# shema.net
KiCad netlist of a schematic drawn in EAGLE
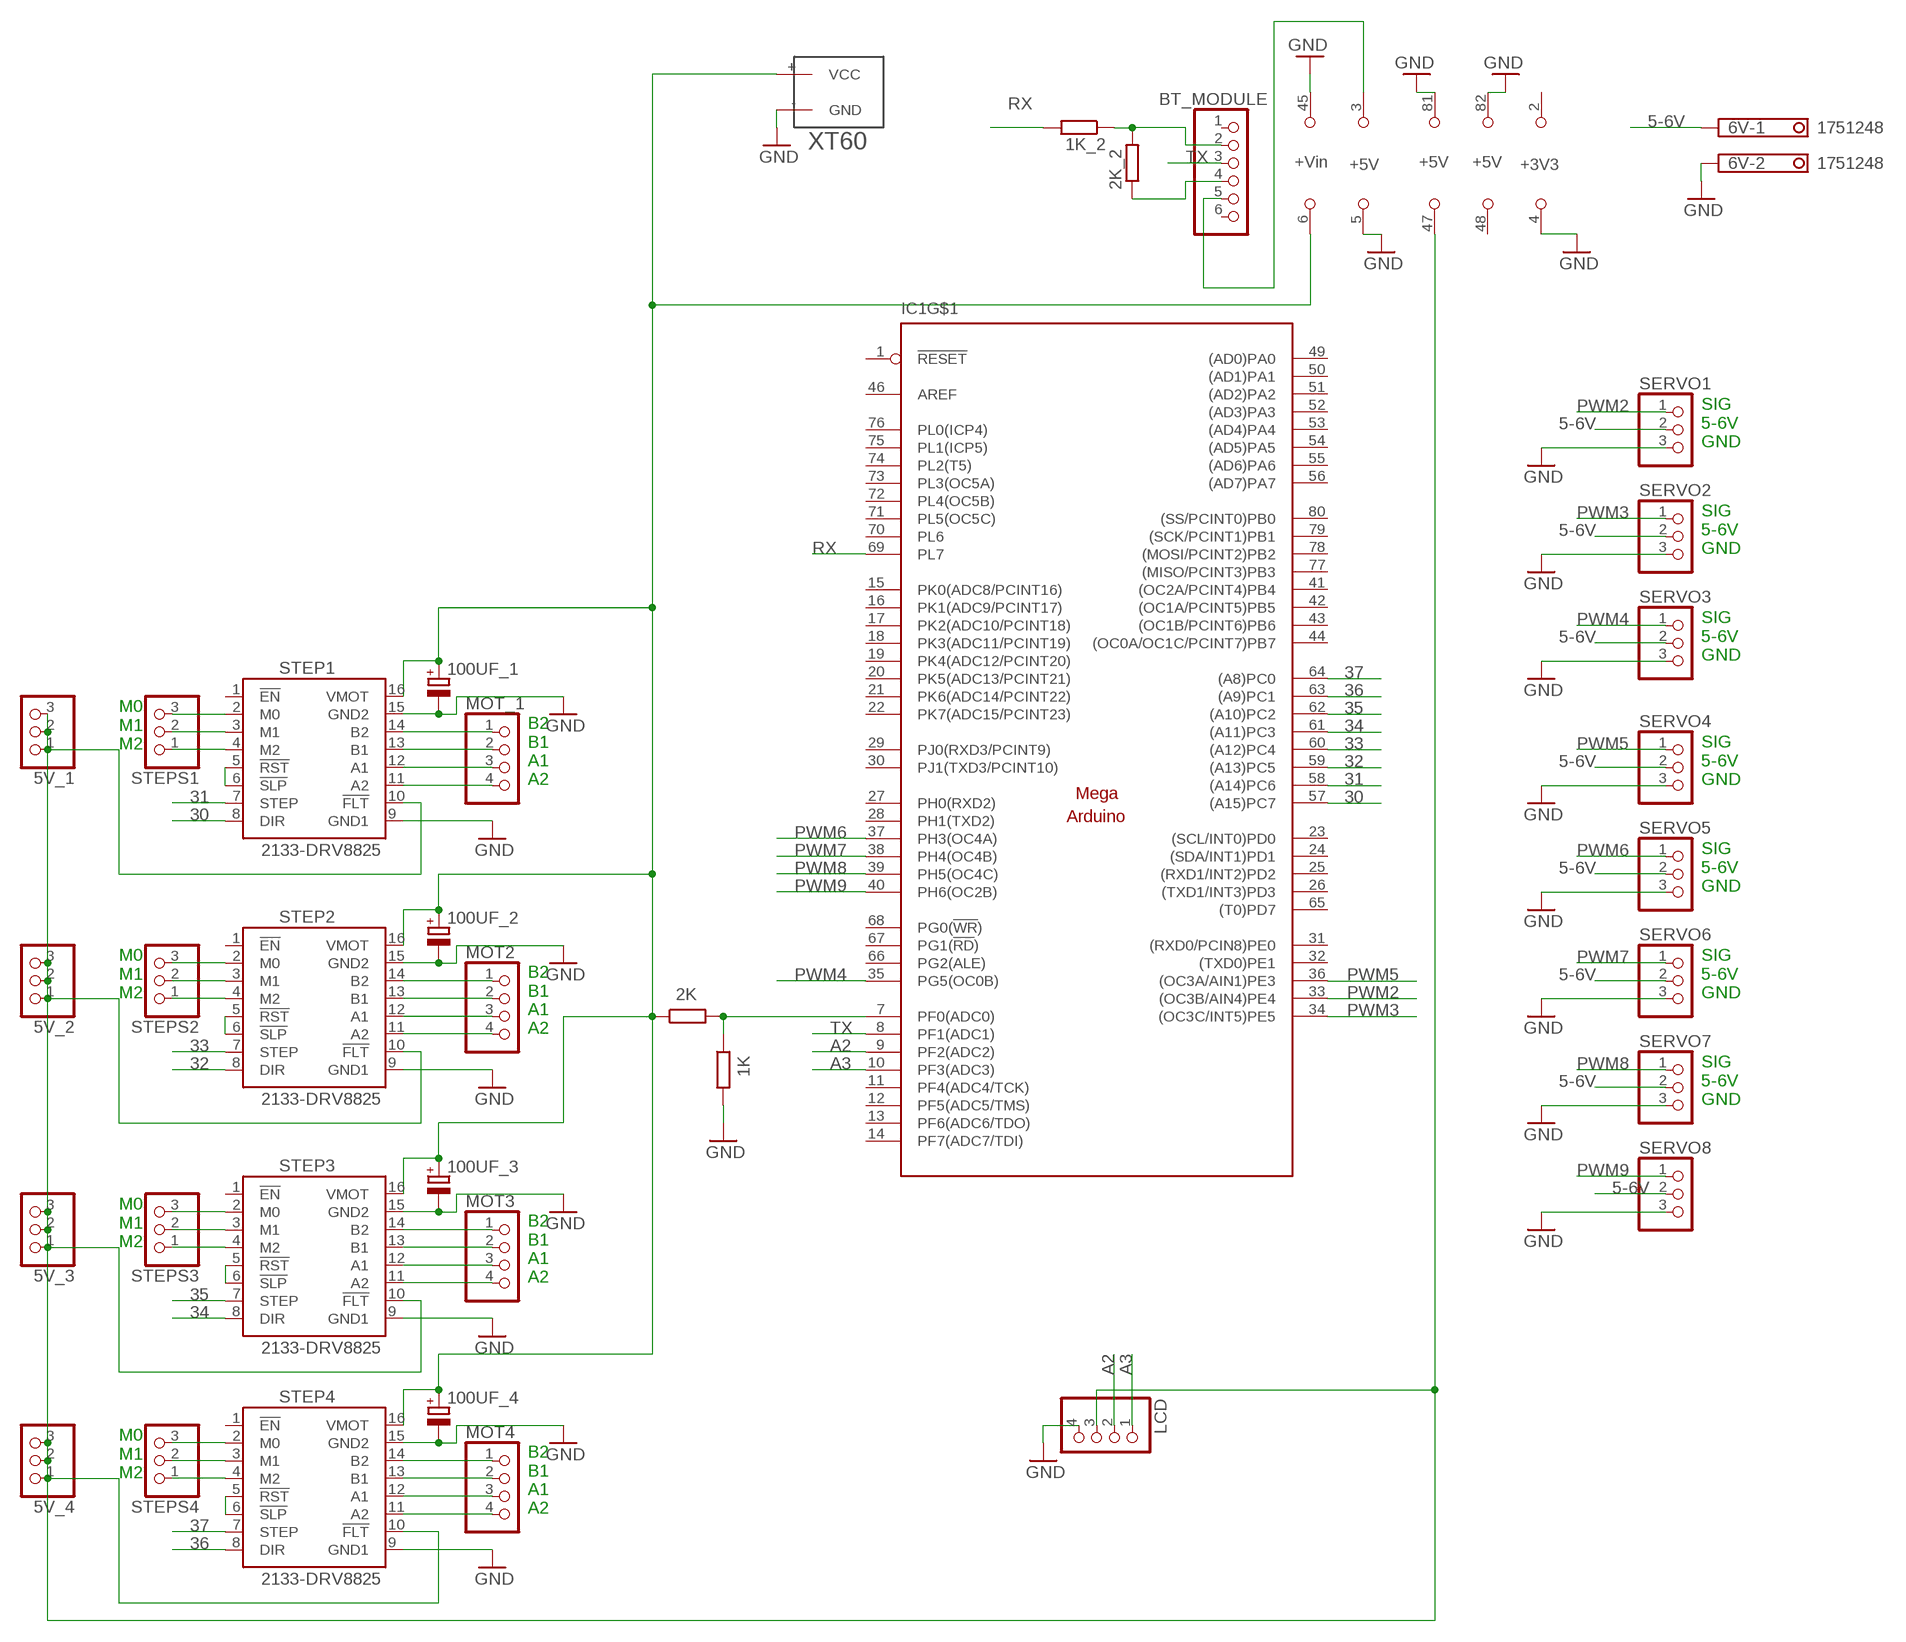
[diagram p0: schematic, sheet 1]

(export (version "E")
  (design (tool "Eeschema 10.0.6"))
  (components
    (comp (ref "1K")
      (value "R-EU_0204/7")
      (footprint "eagle-import:0204_7")
      (libsource (lib "eagle-import") (part "R-EU_0204/7"))
    )
    (comp (ref "1K_2")
      (value "R-EU_0204/7")
      (footprint "eagle-import:0204_7")
      (libsource (lib "eagle-import") (part "R-EU_0204/7"))
    )
    (comp (ref "2K")
      (value "R-EU_0204/7")
      (footprint "eagle-import:0204_7")
      (libsource (lib "eagle-import") (part "R-EU_0204/7"))
    )
    (comp (ref "2K_2")
      (value "R-EU_0204/7")
      (footprint "eagle-import:0204_7")
      (libsource (lib "eagle-import") (part "R-EU_0204/7"))
    )
    (comp (ref "5V_1")
      (value "PINHD-1X3")
      (footprint "eagle-import:1X03")
      (libsource (lib "eagle-import") (part "PINHD-1X3"))
    )
    (comp (ref "5V_2")
      (value "PINHD-1X3")
      (footprint "eagle-import:1X03")
      (libsource (lib "eagle-import") (part "PINHD-1X3"))
    )
    (comp (ref "5V_3")
      (value "PINHD-1X3")
      (footprint "eagle-import:1X03")
      (libsource (lib "eagle-import") (part "PINHD-1X3"))
    )
    (comp (ref "5V_4")
      (value "PINHD-1X3")
      (footprint "eagle-import:1X03")
      (libsource (lib "eagle-import") (part "PINHD-1X3"))
    )
    (comp (ref "6V")
      (value "1751248")
      (footprint "eagle-import:1751248")
      (libsource (lib "eagle-import") (part "1751248"))
    )
    (comp (ref "100UF_1")
      (value "CPOL-EUE5-5")
      (footprint "eagle-import:E5-5")
      (libsource (lib "eagle-import") (part "CPOL-EUE5-5"))
    )
    (comp (ref "100UF_2")
      (value "CPOL-EUE5-5")
      (footprint "eagle-import:E5-5")
      (libsource (lib "eagle-import") (part "CPOL-EUE5-5"))
    )
    (comp (ref "100UF_3")
      (value "CPOL-EUE5-5")
      (footprint "eagle-import:E5-5")
      (libsource (lib "eagle-import") (part "CPOL-EUE5-5"))
    )
    (comp (ref "100UF_4")
      (value "CPOL-EUE5-5")
      (footprint "eagle-import:E5-5")
      (libsource (lib "eagle-import") (part "CPOL-EUE5-5"))
    )
    (comp (ref "BT_MODULE")
      (value "PINHD-1X6")
      (footprint "eagle-import:1X06")
      (libsource (lib "eagle-import") (part "PINHD-1X6"))
    )
    (comp (ref "IC1")
      (value "MEGAARDUINO_22")
      (footprint "eagle-import:MEGA_ARDUINO_2")
      (libsource (lib "eagle-import") (part "MEGAARDUINO_22"))
    )
    (comp (ref "LCD")
      (value "PINHD-1X4")
      (footprint "eagle-import:1X04")
      (libsource (lib "eagle-import") (part "PINHD-1X4"))
    )
    (comp (ref "MOT2")
      (value "PINHD-1X4")
      (footprint "eagle-import:1X04")
      (libsource (lib "eagle-import") (part "PINHD-1X4"))
    )
    (comp (ref "MOT3")
      (value "PINHD-1X4")
      (footprint "eagle-import:1X04")
      (libsource (lib "eagle-import") (part "PINHD-1X4"))
    )
    (comp (ref "MOT4")
      (value "PINHD-1X4")
      (footprint "eagle-import:1X04")
      (libsource (lib "eagle-import") (part "PINHD-1X4"))
    )
    (comp (ref "MOT_1")
      (value "PINHD-1X4")
      (footprint "eagle-import:1X04")
      (libsource (lib "eagle-import") (part "PINHD-1X4"))
    )
    (comp (ref "SERVO1")
      (value "PINHD-1X3")
      (footprint "eagle-import:1X03")
      (libsource (lib "eagle-import") (part "PINHD-1X3"))
    )
    (comp (ref "SERVO2")
      (value "PINHD-1X3")
      (footprint "eagle-import:1X03")
      (libsource (lib "eagle-import") (part "PINHD-1X3"))
    )
    (comp (ref "SERVO3")
      (value "PINHD-1X3")
      (footprint "eagle-import:1X03")
      (libsource (lib "eagle-import") (part "PINHD-1X3"))
    )
    (comp (ref "SERVO4")
      (value "PINHD-1X3")
      (footprint "eagle-import:1X03")
      (libsource (lib "eagle-import") (part "PINHD-1X3"))
    )
    (comp (ref "SERVO5")
      (value "PINHD-1X3")
      (footprint "eagle-import:1X03")
      (libsource (lib "eagle-import") (part "PINHD-1X3"))
    )
    (comp (ref "SERVO6")
      (value "PINHD-1X3")
      (footprint "eagle-import:1X03")
      (libsource (lib "eagle-import") (part "PINHD-1X3"))
    )
    (comp (ref "SERVO7")
      (value "PINHD-1X3")
      (footprint "eagle-import:1X03")
      (libsource (lib "eagle-import") (part "PINHD-1X3"))
    )
    (comp (ref "SERVO8")
      (value "PINHD-1X3")
      (footprint "eagle-import:1X03")
      (libsource (lib "eagle-import") (part "PINHD-1X3"))
    )
    (comp (ref "STEP1")
      (value "2133-DRV8825")
      (footprint "eagle-import:DRV8825")
      (libsource (lib "eagle-import") (part "2133-DRV8825"))
    )
    (comp (ref "STEP2")
      (value "2133-DRV8825")
      (footprint "eagle-import:DRV8825")
      (libsource (lib "eagle-import") (part "2133-DRV8825"))
    )
    (comp (ref "STEP3")
      (value "2133-DRV8825")
      (footprint "eagle-import:DRV8825")
      (libsource (lib "eagle-import") (part "2133-DRV8825"))
    )
    (comp (ref "STEP4")
      (value "2133-DRV8825")
      (footprint "eagle-import:DRV8825")
      (libsource (lib "eagle-import") (part "2133-DRV8825"))
    )
    (comp (ref "STEPS1")
      (value "PINHD-1X3")
      (footprint "eagle-import:1X03")
      (libsource (lib "eagle-import") (part "PINHD-1X3"))
    )
    (comp (ref "STEPS2")
      (value "PINHD-1X3")
      (footprint "eagle-import:1X03")
      (libsource (lib "eagle-import") (part "PINHD-1X3"))
    )
    (comp (ref "STEPS3")
      (value "PINHD-1X3")
      (footprint "eagle-import:1X03")
      (libsource (lib "eagle-import") (part "PINHD-1X3"))
    )
    (comp (ref "STEPS4")
      (value "PINHD-1X3")
      (footprint "eagle-import:1X03")
      (libsource (lib "eagle-import") (part "PINHD-1X3"))
    )
    (comp (ref "U$1")
      (value "XT60")
      (footprint "eagle-import:XT60")
      (libsource (lib "eagle-import") (part "XT60"))
    )
  )
  (nets
    (net (code "1") (name "/+3V3") (class "Default")
      (node (ref "IC1") (pin "2") (pinfunction "+3V3_2") (pintype "power_in"))
    )
    (net (code "2") (name "/+5V") (class "Default")
      (node (ref "IC1") (pin "48") (pinfunction "+5V_48") (pintype "power_in"))
    )
    (net (code "3") (name "/5-6V") (class "Default")
      (node (ref "6V") (pin "1") (pinfunction "K_1") (pintype "passive"))
      (node (ref "SERVO1") (pin "2") (pinfunction "2_2") (pintype "passive"))
      (node (ref "SERVO2") (pin "2") (pinfunction "2_2") (pintype "passive"))
      (node (ref "SERVO3") (pin "2") (pinfunction "2_2") (pintype "passive"))
      (node (ref "SERVO4") (pin "2") (pinfunction "2_2") (pintype "passive"))
      (node (ref "SERVO5") (pin "2") (pinfunction "2_2") (pintype "passive"))
      (node (ref "SERVO6") (pin "2") (pinfunction "2_2") (pintype "passive"))
      (node (ref "SERVO7") (pin "2") (pinfunction "2_2") (pintype "passive"))
      (node (ref "SERVO8") (pin "2") (pinfunction "2_2") (pintype "passive"))
    )
    (net (code "4") (name "/30") (class "Default")
      (node (ref "IC1") (pin "57") (pinfunction "(A15)PC7_57") (pintype "bidirectional"))
      (node (ref "STEP1") (pin "8") (pinfunction "DIR_8") (pintype "input"))
    )
    (net (code "5") (name "/31") (class "Default")
      (node (ref "IC1") (pin "58") (pinfunction "(A14)PC6_58") (pintype "bidirectional"))
      (node (ref "STEP1") (pin "7") (pinfunction "STEP_7") (pintype "input"))
    )
    (net (code "6") (name "/32") (class "Default")
      (node (ref "IC1") (pin "59") (pinfunction "(A13)PC5_59") (pintype "bidirectional"))
      (node (ref "STEP2") (pin "8") (pinfunction "DIR_8") (pintype "input"))
    )
    (net (code "7") (name "/33") (class "Default")
      (node (ref "IC1") (pin "60") (pinfunction "(A12)PC4_60") (pintype "bidirectional"))
      (node (ref "STEP2") (pin "7") (pinfunction "STEP_7") (pintype "input"))
    )
    (net (code "8") (name "/34") (class "Default")
      (node (ref "IC1") (pin "61") (pinfunction "(A11)PC3_61") (pintype "bidirectional"))
      (node (ref "STEP3") (pin "8") (pinfunction "DIR_8") (pintype "input"))
    )
    (net (code "9") (name "/35") (class "Default")
      (node (ref "IC1") (pin "62") (pinfunction "(A10)PC2_62") (pintype "bidirectional"))
      (node (ref "STEP3") (pin "7") (pinfunction "STEP_7") (pintype "input"))
    )
    (net (code "10") (name "/36") (class "Default")
      (node (ref "IC1") (pin "63") (pinfunction "(A9)PC1_63") (pintype "bidirectional"))
      (node (ref "STEP4") (pin "8") (pinfunction "DIR_8") (pintype "input"))
    )
    (net (code "11") (name "/37") (class "Default")
      (node (ref "IC1") (pin "64") (pinfunction "(A8)PC0_64") (pintype "bidirectional"))
      (node (ref "STEP4") (pin "7") (pinfunction "STEP_7") (pintype "input"))
    )
    (net (code "12") (name "/A2") (class "Default")
      (node (ref "IC1") (pin "9") (pinfunction "PF2(ADC2)_9") (pintype "bidirectional"))
      (node (ref "LCD") (pin "2") (pinfunction "2_2") (pintype "passive"))
    )
    (net (code "13") (name "/A3") (class "Default")
      (node (ref "IC1") (pin "10") (pinfunction "PF3(ADC3)_10") (pintype "bidirectional"))
      (node (ref "LCD") (pin "1") (pinfunction "1_1") (pintype "passive"))
    )
    (net (code "14") (name "/PWM2") (class "Default")
      (node (ref "IC1") (pin "33") (pinfunction "(OC3B/AIN4)PE4_33") (pintype "bidirectional"))
      (node (ref "SERVO1") (pin "1") (pinfunction "1_1") (pintype "passive"))
    )
    (net (code "15") (name "/PWM3") (class "Default")
      (node (ref "IC1") (pin "34") (pinfunction "(OC3C/INT5)PE5_34") (pintype "bidirectional"))
      (node (ref "SERVO2") (pin "1") (pinfunction "1_1") (pintype "passive"))
    )
    (net (code "16") (name "/PWM4") (class "Default")
      (node (ref "IC1") (pin "35") (pinfunction "PG5(OC0B)_35") (pintype "bidirectional"))
      (node (ref "SERVO3") (pin "1") (pinfunction "1_1") (pintype "passive"))
    )
    (net (code "17") (name "/PWM5") (class "Default")
      (node (ref "IC1") (pin "36") (pinfunction "(OC3A/AIN1)PE3_36") (pintype "bidirectional"))
      (node (ref "SERVO4") (pin "1") (pinfunction "1_1") (pintype "passive"))
    )
    (net (code "18") (name "/PWM6") (class "Default")
      (node (ref "IC1") (pin "37") (pinfunction "PH3(OC4A)_37") (pintype "bidirectional"))
      (node (ref "SERVO5") (pin "1") (pinfunction "1_1") (pintype "passive"))
    )
    (net (code "19") (name "/PWM7") (class "Default")
      (node (ref "IC1") (pin "38") (pinfunction "PH4(OC4B)_38") (pintype "bidirectional"))
      (node (ref "SERVO6") (pin "1") (pinfunction "1_1") (pintype "passive"))
    )
    (net (code "20") (name "/PWM8") (class "Default")
      (node (ref "IC1") (pin "39") (pinfunction "PH5(OC4C)_39") (pintype "bidirectional"))
      (node (ref "SERVO7") (pin "1") (pinfunction "1_1") (pintype "passive"))
    )
    (net (code "21") (name "/PWM9") (class "Default")
      (node (ref "IC1") (pin "40") (pinfunction "PH6(OC2B)_40") (pintype "bidirectional"))
      (node (ref "SERVO8") (pin "1") (pinfunction "1_1") (pintype "passive"))
    )
    (net (code "22") (name "/RX") (class "Default")
      (node (ref "1K_2") (pin "2") (pinfunction "2_2") (pintype "passive"))
      (node (ref "IC1") (pin "69") (pinfunction "PL7_69") (pintype "bidirectional"))
    )
    (net (code "23") (name "/TX") (class "Default")
      (node (ref "BT_MODULE") (pin "3") (pinfunction "3_3") (pintype "passive"))
      (node (ref "IC1") (pin "8") (pinfunction "PF1(ADC1)_8") (pintype "bidirectional"))
    )
    (net (code "24") (name "GND") (class "Default")
      (node (ref "100UF_1") (pin "-") (pinfunction "-_-") (pintype "passive"))
      (node (ref "100UF_2") (pin "-") (pinfunction "-_-") (pintype "passive"))
      (node (ref "100UF_3") (pin "-") (pinfunction "-_-") (pintype "passive"))
      (node (ref "100UF_4") (pin "-") (pinfunction "-_-") (pintype "passive"))
      (node (ref "1K") (pin "2") (pinfunction "2_2") (pintype "passive"))
      (node (ref "6V") (pin "2") (pinfunction "K_2") (pintype "passive"))
      (node (ref "IC1") (pin "4") (pinfunction "GND_4") (pintype "power_in"))
      (node (ref "IC1") (pin "45") (pinfunction "GND_45") (pintype "power_in"))
      (node (ref "IC1") (pin "5") (pinfunction "GND_5") (pintype "power_in"))
      (node (ref "IC1") (pin "81") (pinfunction "GND_81") (pintype "power_in"))
      (node (ref "IC1") (pin "82") (pinfunction "GND_82") (pintype "power_in"))
      (node (ref "LCD") (pin "4") (pinfunction "4_4") (pintype "passive"))
      (node (ref "SERVO1") (pin "3") (pinfunction "3_3") (pintype "passive"))
      (node (ref "SERVO2") (pin "3") (pinfunction "3_3") (pintype "passive"))
      (node (ref "SERVO3") (pin "3") (pinfunction "3_3") (pintype "passive"))
      (node (ref "SERVO4") (pin "3") (pinfunction "3_3") (pintype "passive"))
      (node (ref "SERVO5") (pin "3") (pinfunction "3_3") (pintype "passive"))
      (node (ref "SERVO6") (pin "3") (pinfunction "3_3") (pintype "passive"))
      (node (ref "SERVO7") (pin "3") (pinfunction "3_3") (pintype "passive"))
      (node (ref "SERVO8") (pin "3") (pinfunction "3_3") (pintype "passive"))
      (node (ref "STEP1") (pin "15") (pinfunction "GND2_15") (pintype "power_in"))
      (node (ref "STEP1") (pin "9") (pinfunction "GND1_9") (pintype "power_in"))
      (node (ref "STEP2") (pin "15") (pinfunction "GND2_15") (pintype "power_in"))
      (node (ref "STEP2") (pin "9") (pinfunction "GND1_9") (pintype "power_in"))
      (node (ref "STEP3") (pin "15") (pinfunction "GND2_15") (pintype "power_in"))
      (node (ref "STEP3") (pin "9") (pinfunction "GND1_9") (pintype "power_in"))
      (node (ref "STEP4") (pin "15") (pinfunction "GND2_15") (pintype "power_in"))
      (node (ref "STEP4") (pin "9") (pinfunction "GND1_9") (pintype "power_in"))
      (node (ref "U$1") (pin "-") (pinfunction "GND_-") (pintype "bidirectional"))
    )
    (net (code "25") (name "Net-(1K_2-Pad1)") (class "Default")
      (node (ref "1K_2") (pin "1") (pinfunction "1_1") (pintype "passive"))
      (node (ref "2K_2") (pin "2") (pinfunction "2_2") (pintype "passive"))
      (node (ref "BT_MODULE") (pin "2") (pinfunction "2_2") (pintype "passive"))
    )
    (net (code "26") (name "Net-(2K_2-Pad1)") (class "Default")
      (node (ref "2K_2") (pin "1") (pinfunction "1_1") (pintype "passive"))
      (node (ref "BT_MODULE") (pin "4") (pinfunction "4_4") (pintype "passive"))
    )
    (net (code "27") (name "Net-(IC1A-PF0(ADC0))") (class "Default")
      (node (ref "1K") (pin "1") (pinfunction "1_1") (pintype "passive"))
      (node (ref "2K") (pin "2") (pinfunction "2_2") (pintype "passive"))
      (node (ref "IC1") (pin "7") (pinfunction "PF0(ADC0)_7") (pintype "bidirectional"))
    )
    (net (code "28") (name "Net-(IC1B-+5V)") (class "Default")
      (node (ref "BT_MODULE") (pin "5") (pinfunction "5_5") (pintype "passive"))
      (node (ref "IC1") (pin "3") (pinfunction "+5V_3") (pintype "power_in"))
    )
    (net (code "29") (name "Net-(IC1C-+5V)") (class "Default")
      (node (ref "5V_1") (pin "1") (pinfunction "1_1") (pintype "passive"))
      (node (ref "5V_1") (pin "2") (pinfunction "2_2") (pintype "passive"))
      (node (ref "5V_1") (pin "3") (pinfunction "3_3") (pintype "passive"))
      (node (ref "5V_2") (pin "1") (pinfunction "1_1") (pintype "passive"))
      (node (ref "5V_2") (pin "2") (pinfunction "2_2") (pintype "passive"))
      (node (ref "5V_2") (pin "3") (pinfunction "3_3") (pintype "passive"))
      (node (ref "5V_3") (pin "1") (pinfunction "1_1") (pintype "passive"))
      (node (ref "5V_3") (pin "2") (pinfunction "2_2") (pintype "passive"))
      (node (ref "5V_3") (pin "3") (pinfunction "3_3") (pintype "passive"))
      (node (ref "5V_4") (pin "1") (pinfunction "1_1") (pintype "passive"))
      (node (ref "5V_4") (pin "2") (pinfunction "2_2") (pintype "passive"))
      (node (ref "5V_4") (pin "3") (pinfunction "3_3") (pintype "passive"))
      (node (ref "IC1") (pin "47") (pinfunction "+5V_47") (pintype "power_in"))
      (node (ref "LCD") (pin "3") (pinfunction "3_3") (pintype "passive"))
      (node (ref "STEP1") (pin "10") (pinfunction "~{FLT}_10") (pintype "open_collector"))
      (node (ref "STEP2") (pin "10") (pinfunction "~{FLT}_10") (pintype "open_collector"))
      (node (ref "STEP3") (pin "10") (pinfunction "~{FLT}_10") (pintype "open_collector"))
      (node (ref "STEP4") (pin "10") (pinfunction "~{FLT}_10") (pintype "open_collector"))
    )
    (net (code "30") (name "Net-(IC1F-+VIN)") (class "Default")
      (node (ref "100UF_1") (pin "+") (pinfunction "+_+") (pintype "passive"))
      (node (ref "100UF_2") (pin "+") (pinfunction "+_+") (pintype "passive"))
      (node (ref "100UF_3") (pin "+") (pinfunction "+_+") (pintype "passive"))
      (node (ref "100UF_4") (pin "+") (pinfunction "+_+") (pintype "passive"))
      (node (ref "2K") (pin "1") (pinfunction "1_1") (pintype "passive"))
      (node (ref "IC1") (pin "6") (pinfunction "+VIN_6") (pintype "power_in"))
      (node (ref "STEP1") (pin "16") (pinfunction "VMOT_16") (pintype "power_in"))
      (node (ref "STEP2") (pin "16") (pinfunction "VMOT_16") (pintype "power_in"))
      (node (ref "STEP3") (pin "16") (pinfunction "VMOT_16") (pintype "power_in"))
      (node (ref "STEP4") (pin "16") (pinfunction "VMOT_16") (pintype "power_in"))
      (node (ref "U$1") (pin "+") (pinfunction "VCC_+") (pintype "bidirectional"))
    )
    (net (code "31") (name "Net-(STEP1-A1)") (class "Default")
      (node (ref "MOT_1") (pin "3") (pinfunction "3_3") (pintype "passive"))
      (node (ref "STEP1") (pin "12") (pinfunction "A1_12") (pintype "output"))
    )
    (net (code "32") (name "Net-(STEP1-A2)") (class "Default")
      (node (ref "MOT_1") (pin "4") (pinfunction "4_4") (pintype "passive"))
      (node (ref "STEP1") (pin "11") (pinfunction "A2_11") (pintype "output"))
    )
    (net (code "33") (name "Net-(STEP1-B1)") (class "Default")
      (node (ref "MOT_1") (pin "2") (pinfunction "2_2") (pintype "passive"))
      (node (ref "STEP1") (pin "13") (pinfunction "B1_13") (pintype "output"))
    )
    (net (code "34") (name "Net-(STEP1-B2)") (class "Default")
      (node (ref "MOT_1") (pin "1") (pinfunction "1_1") (pintype "passive"))
      (node (ref "STEP1") (pin "14") (pinfunction "B2_14") (pintype "output"))
    )
    (net (code "35") (name "Net-(STEP1-M0)") (class "Default")
      (node (ref "STEP1") (pin "2") (pinfunction "M0_2") (pintype "passive"))
      (node (ref "STEPS1") (pin "3") (pinfunction "3_3") (pintype "passive"))
    )
    (net (code "36") (name "Net-(STEP1-M1)") (class "Default")
      (node (ref "STEP1") (pin "3") (pinfunction "M1_3") (pintype "passive"))
      (node (ref "STEPS1") (pin "2") (pinfunction "2_2") (pintype "passive"))
    )
    (net (code "37") (name "Net-(STEP1-M2)") (class "Default")
      (node (ref "STEP1") (pin "4") (pinfunction "M2_4") (pintype "passive"))
      (node (ref "STEPS1") (pin "1") (pinfunction "1_1") (pintype "passive"))
    )
    (net (code "38") (name "Net-(STEP1-~{RST})") (class "Default")
      (node (ref "STEP1") (pin "5") (pinfunction "~{RST}_5") (pintype "input"))
      (node (ref "STEP1") (pin "6") (pinfunction "~{SLP}_6") (pintype "input"))
    )
    (net (code "39") (name "Net-(STEP2-A1)") (class "Default")
      (node (ref "MOT2") (pin "3") (pinfunction "3_3") (pintype "passive"))
      (node (ref "STEP2") (pin "12") (pinfunction "A1_12") (pintype "output"))
    )
    (net (code "40") (name "Net-(STEP2-A2)") (class "Default")
      (node (ref "MOT2") (pin "4") (pinfunction "4_4") (pintype "passive"))
      (node (ref "STEP2") (pin "11") (pinfunction "A2_11") (pintype "output"))
    )
    (net (code "41") (name "Net-(STEP2-B1)") (class "Default")
      (node (ref "MOT2") (pin "2") (pinfunction "2_2") (pintype "passive"))
      (node (ref "STEP2") (pin "13") (pinfunction "B1_13") (pintype "output"))
    )
    (net (code "42") (name "Net-(STEP2-B2)") (class "Default")
      (node (ref "MOT2") (pin "1") (pinfunction "1_1") (pintype "passive"))
      (node (ref "STEP2") (pin "14") (pinfunction "B2_14") (pintype "output"))
    )
    (net (code "43") (name "Net-(STEP2-M0)") (class "Default")
      (node (ref "STEP2") (pin "2") (pinfunction "M0_2") (pintype "passive"))
      (node (ref "STEPS2") (pin "3") (pinfunction "3_3") (pintype "passive"))
    )
    (net (code "44") (name "Net-(STEP2-M1)") (class "Default")
      (node (ref "STEP2") (pin "3") (pinfunction "M1_3") (pintype "passive"))
      (node (ref "STEPS2") (pin "2") (pinfunction "2_2") (pintype "passive"))
    )
    (net (code "45") (name "Net-(STEP2-M2)") (class "Default")
      (node (ref "STEP2") (pin "4") (pinfunction "M2_4") (pintype "passive"))
      (node (ref "STEPS2") (pin "1") (pinfunction "1_1") (pintype "passive"))
    )
    (net (code "46") (name "Net-(STEP2-~{RST})") (class "Default")
      (node (ref "STEP2") (pin "5") (pinfunction "~{RST}_5") (pintype "input"))
      (node (ref "STEP2") (pin "6") (pinfunction "~{SLP}_6") (pintype "input"))
    )
    (net (code "47") (name "Net-(STEP3-A1)") (class "Default")
      (node (ref "MOT3") (pin "3") (pinfunction "3_3") (pintype "passive"))
      (node (ref "STEP3") (pin "12") (pinfunction "A1_12") (pintype "output"))
    )
    (net (code "48") (name "Net-(STEP3-A2)") (class "Default")
      (node (ref "MOT3") (pin "4") (pinfunction "4_4") (pintype "passive"))
      (node (ref "STEP3") (pin "11") (pinfunction "A2_11") (pintype "output"))
    )
    (net (code "49") (name "Net-(STEP3-B1)") (class "Default")
      (node (ref "MOT3") (pin "2") (pinfunction "2_2") (pintype "passive"))
      (node (ref "STEP3") (pin "13") (pinfunction "B1_13") (pintype "output"))
    )
    (net (code "50") (name "Net-(STEP3-B2)") (class "Default")
      (node (ref "MOT3") (pin "1") (pinfunction "1_1") (pintype "passive"))
      (node (ref "STEP3") (pin "14") (pinfunction "B2_14") (pintype "output"))
    )
    (net (code "51") (name "Net-(STEP3-M0)") (class "Default")
      (node (ref "STEP3") (pin "2") (pinfunction "M0_2") (pintype "passive"))
      (node (ref "STEPS3") (pin "3") (pinfunction "3_3") (pintype "passive"))
    )
    (net (code "52") (name "Net-(STEP3-M1)") (class "Default")
      (node (ref "STEP3") (pin "3") (pinfunction "M1_3") (pintype "passive"))
      (node (ref "STEPS3") (pin "2") (pinfunction "2_2") (pintype "passive"))
    )
    (net (code "53") (name "Net-(STEP3-M2)") (class "Default")
      (node (ref "STEP3") (pin "4") (pinfunction "M2_4") (pintype "passive"))
      (node (ref "STEPS3") (pin "1") (pinfunction "1_1") (pintype "passive"))
    )
    (net (code "54") (name "Net-(STEP3-~{RST})") (class "Default")
      (node (ref "STEP3") (pin "5") (pinfunction "~{RST}_5") (pintype "input"))
      (node (ref "STEP3") (pin "6") (pinfunction "~{SLP}_6") (pintype "input"))
    )
    (net (code "55") (name "Net-(STEP4-A1)") (class "Default")
      (node (ref "MOT4") (pin "3") (pinfunction "3_3") (pintype "passive"))
      (node (ref "STEP4") (pin "12") (pinfunction "A1_12") (pintype "output"))
    )
    (net (code "56") (name "Net-(STEP4-A2)") (class "Default")
      (node (ref "MOT4") (pin "4") (pinfunction "4_4") (pintype "passive"))
      (node (ref "STEP4") (pin "11") (pinfunction "A2_11") (pintype "output"))
    )
    (net (code "57") (name "Net-(STEP4-B1)") (class "Default")
      (node (ref "MOT4") (pin "2") (pinfunction "2_2") (pintype "passive"))
      (node (ref "STEP4") (pin "13") (pinfunction "B1_13") (pintype "output"))
    )
    (net (code "58") (name "Net-(STEP4-B2)") (class "Default")
      (node (ref "MOT4") (pin "1") (pinfunction "1_1") (pintype "passive"))
      (node (ref "STEP4") (pin "14") (pinfunction "B2_14") (pintype "output"))
    )
    (net (code "59") (name "Net-(STEP4-M0)") (class "Default")
      (node (ref "STEP4") (pin "2") (pinfunction "M0_2") (pintype "passive"))
      (node (ref "STEPS4") (pin "3") (pinfunction "3_3") (pintype "passive"))
    )
    (net (code "60") (name "Net-(STEP4-M1)") (class "Default")
      (node (ref "STEP4") (pin "3") (pinfunction "M1_3") (pintype "passive"))
      (node (ref "STEPS4") (pin "2") (pinfunction "2_2") (pintype "passive"))
    )
    (net (code "61") (name "Net-(STEP4-M2)") (class "Default")
      (node (ref "STEP4") (pin "4") (pinfunction "M2_4") (pintype "passive"))
      (node (ref "STEPS4") (pin "1") (pinfunction "1_1") (pintype "passive"))
    )
    (net (code "62") (name "Net-(STEP4-~{RST})") (class "Default")
      (node (ref "STEP4") (pin "5") (pinfunction "~{RST}_5") (pintype "input"))
      (node (ref "STEP4") (pin "6") (pinfunction "~{SLP}_6") (pintype "input"))
    )
    (net (code "63") (name "unconnected-(BT_MODULE-Pad1)") (class "Default")
      (node (ref "BT_MODULE") (pin "1") (pinfunction "1_1") (pintype "passive"))
    )
    (net (code "64") (name "unconnected-(BT_MODULE-Pad6)") (class "Default")
      (node (ref "BT_MODULE") (pin "6") (pinfunction "6_6") (pintype "passive"))
    )
    (net (code "65") (name "unconnected-(IC1A-(AD0)PA0-Pad49)") (class "Default")
      (node (ref "IC1") (pin "49") (pinfunction "(AD0)PA0_49") (pintype "bidirectional"))
    )
    (net (code "66") (name "unconnected-(IC1A-(AD1)PA1-Pad50)") (class "Default")
      (node (ref "IC1") (pin "50") (pinfunction "(AD1)PA1_50") (pintype "bidirectional"))
    )
    (net (code "67") (name "unconnected-(IC1A-(AD2)PA2-Pad51)") (class "Default")
      (node (ref "IC1") (pin "51") (pinfunction "(AD2)PA2_51") (pintype "bidirectional"))
    )
    (net (code "68") (name "unconnected-(IC1A-(AD3)PA3-Pad52)") (class "Default")
      (node (ref "IC1") (pin "52") (pinfunction "(AD3)PA3_52") (pintype "bidirectional"))
    )
    (net (code "69") (name "unconnected-(IC1A-(AD4)PA4-Pad53)") (class "Default")
      (node (ref "IC1") (pin "53") (pinfunction "(AD4)PA4_53") (pintype "bidirectional"))
    )
    (net (code "70") (name "unconnected-(IC1A-(AD5)PA5-Pad54)") (class "Default")
      (node (ref "IC1") (pin "54") (pinfunction "(AD5)PA5_54") (pintype "bidirectional"))
    )
    (net (code "71") (name "unconnected-(IC1A-(AD6)PA6-Pad55)") (class "Default")
      (node (ref "IC1") (pin "55") (pinfunction "(AD6)PA6_55") (pintype "bidirectional"))
    )
    (net (code "72") (name "unconnected-(IC1A-(AD7)PA7-Pad56)") (class "Default")
      (node (ref "IC1") (pin "56") (pinfunction "(AD7)PA7_56") (pintype "bidirectional"))
    )
    (net (code "73") (name "unconnected-(IC1A-(MISO{slash}PCINT3)PB3-Pad77)") (class "Default")
      (node (ref "IC1") (pin "77") (pinfunction "(MISO/PCINT3)PB3_77") (pintype "bidirectional"))
    )
    (net (code "74") (name "unconnected-(IC1A-(MOSI{slash}PCINT2)PB2-Pad78)") (class "Default")
      (node (ref "IC1") (pin "78") (pinfunction "(MOSI/PCINT2)PB2_78") (pintype "bidirectional"))
    )
    (net (code "75") (name "unconnected-(IC1A-(OC0A{slash}OC1C{slash}PCINT7)PB7-Pad44)") (class "Default")
      (node (ref "IC1") (pin "44") (pinfunction "(OC0A/OC1C/PCINT7)PB7_44") (pintype "bidirectional"))
    )
    (net (code "76") (name "unconnected-(IC1A-(OC1A{slash}PCINT5)PB5-Pad42)") (class "Default")
      (node (ref "IC1") (pin "42") (pinfunction "(OC1A/PCINT5)PB5_42") (pintype "bidirectional"))
    )
    (net (code "77") (name "unconnected-(IC1A-(OC1B{slash}PCINT6)PB6-Pad43)") (class "Default")
      (node (ref "IC1") (pin "43") (pinfunction "(OC1B/PCINT6)PB6_43") (pintype "bidirectional"))
    )
    (net (code "78") (name "unconnected-(IC1A-(OC2A{slash}PCINT4)PB4-Pad41)") (class "Default")
      (node (ref "IC1") (pin "41") (pinfunction "(OC2A/PCINT4)PB4_41") (pintype "bidirectional"))
    )
    (net (code "79") (name "unconnected-(IC1A-(RXD0{slash}PCIN8)PE0-Pad31)") (class "Default")
      (node (ref "IC1") (pin "31") (pinfunction "(RXD0/PCIN8)PE0_31") (pintype "bidirectional"))
    )
    (net (code "80") (name "unconnected-(IC1A-(RXD1{slash}INT2)PD2-Pad25)") (class "Default")
      (node (ref "IC1") (pin "25") (pinfunction "(RXD1/INT2)PD2_25") (pintype "bidirectional"))
    )
    (net (code "81") (name "unconnected-(IC1A-(SCK{slash}PCINT1)PB1-Pad79)") (class "Default")
      (node (ref "IC1") (pin "79") (pinfunction "(SCK/PCINT1)PB1_79") (pintype "bidirectional"))
    )
    (net (code "82") (name "unconnected-(IC1A-(SCL{slash}INT0)PD0-Pad23)") (class "Default")
      (node (ref "IC1") (pin "23") (pinfunction "(SCL/INT0)PD0_23") (pintype "bidirectional"))
    )
    (net (code "83") (name "unconnected-(IC1A-(SDA{slash}INT1)PD1-Pad24)") (class "Default")
      (node (ref "IC1") (pin "24") (pinfunction "(SDA/INT1)PD1_24") (pintype "bidirectional"))
    )
    (net (code "84") (name "unconnected-(IC1A-(SS{slash}PCINT0)PB0-Pad80)") (class "Default")
      (node (ref "IC1") (pin "80") (pinfunction "(SS/PCINT0)PB0_80") (pintype "bidirectional"))
    )
    (net (code "85") (name "unconnected-(IC1A-(T0)PD7-Pad65)") (class "Default")
      (node (ref "IC1") (pin "65") (pinfunction "(T0)PD7_65") (pintype "bidirectional"))
    )
    (net (code "86") (name "unconnected-(IC1A-(TXD0)PE1-Pad32)") (class "Default")
      (node (ref "IC1") (pin "32") (pinfunction "(TXD0)PE1_32") (pintype "bidirectional"))
    )
    (net (code "87") (name "unconnected-(IC1A-(TXD1{slash}INT3)PD3-Pad26)") (class "Default")
      (node (ref "IC1") (pin "26") (pinfunction "(TXD1/INT3)PD3_26") (pintype "bidirectional"))
    )
    (net (code "88") (name "unconnected-(IC1A-AREF-Pad46)") (class "Default")
      (node (ref "IC1") (pin "46") (pinfunction "AREF_46") (pintype "bidirectional"))
    )
    (net (code "89") (name "unconnected-(IC1A-PF4(ADC4{slash}TCK)-Pad11)") (class "Default")
      (node (ref "IC1") (pin "11") (pinfunction "PF4(ADC4/TCK)_11") (pintype "bidirectional"))
    )
    (net (code "90") (name "unconnected-(IC1A-PF5(ADC5{slash}TMS)-Pad12)") (class "Default")
      (node (ref "IC1") (pin "12") (pinfunction "PF5(ADC5/TMS)_12") (pintype "bidirectional"))
    )
    (net (code "91") (name "unconnected-(IC1A-PF6(ADC6{slash}TDO)-Pad13)") (class "Default")
      (node (ref "IC1") (pin "13") (pinfunction "PF6(ADC6/TDO)_13") (pintype "bidirectional"))
    )
    (net (code "92") (name "unconnected-(IC1A-PF7(ADC7{slash}TDI)-Pad14)") (class "Default")
      (node (ref "IC1") (pin "14") (pinfunction "PF7(ADC7/TDI)_14") (pintype "bidirectional"))
    )
    (net (code "93") (name "unconnected-(IC1A-PG0(~{WR})-Pad68)") (class "Default")
      (node (ref "IC1") (pin "68") (pinfunction "PG0(~{WR})_68") (pintype "bidirectional"))
    )
    (net (code "94") (name "unconnected-(IC1A-PG1(~{RD})-Pad67)") (class "Default")
      (node (ref "IC1") (pin "67") (pinfunction "PG1(~{RD})_67") (pintype "bidirectional"))
    )
    (net (code "95") (name "unconnected-(IC1A-PG2(ALE)-Pad66)") (class "Default")
      (node (ref "IC1") (pin "66") (pinfunction "PG2(ALE)_66") (pintype "bidirectional"))
    )
    (net (code "96") (name "unconnected-(IC1A-PH0(RXD2)-Pad27)") (class "Default")
      (node (ref "IC1") (pin "27") (pinfunction "PH0(RXD2)_27") (pintype "bidirectional"))
    )
    (net (code "97") (name "unconnected-(IC1A-PH1(TXD2)-Pad28)") (class "Default")
      (node (ref "IC1") (pin "28") (pinfunction "PH1(TXD2)_28") (pintype "bidirectional"))
    )
    (net (code "98") (name "unconnected-(IC1A-PJ0(RXD3{slash}PCINT9)-Pad29)") (class "Default")
      (node (ref "IC1") (pin "29") (pinfunction "PJ0(RXD3/PCINT9)_29") (pintype "bidirectional"))
    )
    (net (code "99") (name "unconnected-(IC1A-PJ1(TXD3{slash}PCINT10)-Pad30)") (class "Default")
      (node (ref "IC1") (pin "30") (pinfunction "PJ1(TXD3/PCINT10)_30") (pintype "bidirectional"))
    )
    (net (code "100") (name "unconnected-(IC1A-PK0(ADC8{slash}PCINT16)-Pad15)") (class "Default")
      (node (ref "IC1") (pin "15") (pinfunction "PK0(ADC8/PCINT16)_15") (pintype "bidirectional"))
    )
    (net (code "101") (name "unconnected-(IC1A-PK1(ADC9{slash}PCINT17)-Pad16)") (class "Default")
      (node (ref "IC1") (pin "16") (pinfunction "PK1(ADC9/PCINT17)_16") (pintype "bidirectional"))
    )
    (net (code "102") (name "unconnected-(IC1A-PK2(ADC10{slash}PCINT18)-Pad17)") (class "Default")
      (node (ref "IC1") (pin "17") (pinfunction "PK2(ADC10/PCINT18)_17") (pintype "bidirectional"))
    )
    (net (code "103") (name "unconnected-(IC1A-PK3(ADC11{slash}PCINT19)-Pad18)") (class "Default")
      (node (ref "IC1") (pin "18") (pinfunction "PK3(ADC11/PCINT19)_18") (pintype "bidirectional"))
    )
    (net (code "104") (name "unconnected-(IC1A-PK4(ADC12{slash}PCINT20)-Pad19)") (class "Default")
      (node (ref "IC1") (pin "19") (pinfunction "PK4(ADC12/PCINT20)_19") (pintype "bidirectional"))
    )
    (net (code "105") (name "unconnected-(IC1A-PK5(ADC13{slash}PCINT21)-Pad20)") (class "Default")
      (node (ref "IC1") (pin "20") (pinfunction "PK5(ADC13/PCINT21)_20") (pintype "bidirectional"))
    )
    (net (code "106") (name "unconnected-(IC1A-PK6(ADC14{slash}PCINT22)-Pad21)") (class "Default")
      (node (ref "IC1") (pin "21") (pinfunction "PK6(ADC14/PCINT22)_21") (pintype "bidirectional"))
    )
    (net (code "107") (name "unconnected-(IC1A-PK7(ADC15{slash}PCINT23)-Pad22)") (class "Default")
      (node (ref "IC1") (pin "22") (pinfunction "PK7(ADC15/PCINT23)_22") (pintype "bidirectional"))
    )
    (net (code "108") (name "unconnected-(IC1A-PL0(ICP4)-Pad76)") (class "Default")
      (node (ref "IC1") (pin "76") (pinfunction "PL0(ICP4)_76") (pintype "bidirectional"))
    )
    (net (code "109") (name "unconnected-(IC1A-PL1(ICP5)-Pad75)") (class "Default")
      (node (ref "IC1") (pin "75") (pinfunction "PL1(ICP5)_75") (pintype "bidirectional"))
    )
    (net (code "110") (name "unconnected-(IC1A-PL2(T5)-Pad74)") (class "Default")
      (node (ref "IC1") (pin "74") (pinfunction "PL2(T5)_74") (pintype "bidirectional"))
    )
    (net (code "111") (name "unconnected-(IC1A-PL3(OC5A)-Pad73)") (class "Default")
      (node (ref "IC1") (pin "73") (pinfunction "PL3(OC5A)_73") (pintype "bidirectional"))
    )
    (net (code "112") (name "unconnected-(IC1A-PL4(OC5B)-Pad72)") (class "Default")
      (node (ref "IC1") (pin "72") (pinfunction "PL4(OC5B)_72") (pintype "bidirectional"))
    )
    (net (code "113") (name "unconnected-(IC1A-PL5(OC5C)-Pad71)") (class "Default")
      (node (ref "IC1") (pin "71") (pinfunction "PL5(OC5C)_71") (pintype "bidirectional"))
    )
    (net (code "114") (name "unconnected-(IC1A-PL6-Pad70)") (class "Default")
      (node (ref "IC1") (pin "70") (pinfunction "PL6_70") (pintype "bidirectional"))
    )
    (net (code "115") (name "unconnected-(IC1A-~{RESET}-Pad1)") (class "Default")
      (node (ref "IC1") (pin "1") (pinfunction "~{RESET}_1") (pintype "bidirectional"))
    )
    (net (code "116") (name "unconnected-(STEP1-~{EN}-Pad1)") (class "Default")
      (node (ref "STEP1") (pin "1") (pinfunction "~{EN}_1") (pintype "passive"))
    )
    (net (code "117") (name "unconnected-(STEP2-~{EN}-Pad1)") (class "Default")
      (node (ref "STEP2") (pin "1") (pinfunction "~{EN}_1") (pintype "passive"))
    )
    (net (code "118") (name "unconnected-(STEP3-~{EN}-Pad1)") (class "Default")
      (node (ref "STEP3") (pin "1") (pinfunction "~{EN}_1") (pintype "passive"))
    )
    (net (code "119") (name "unconnected-(STEP4-~{EN}-Pad1)") (class "Default")
      (node (ref "STEP4") (pin "1") (pinfunction "~{EN}_1") (pintype "passive"))
    )
  )
)
